# PCB_DYBoard_Collector_V1_Sh1.net
KiCad netlist of a schematic drawn in Altium Designer
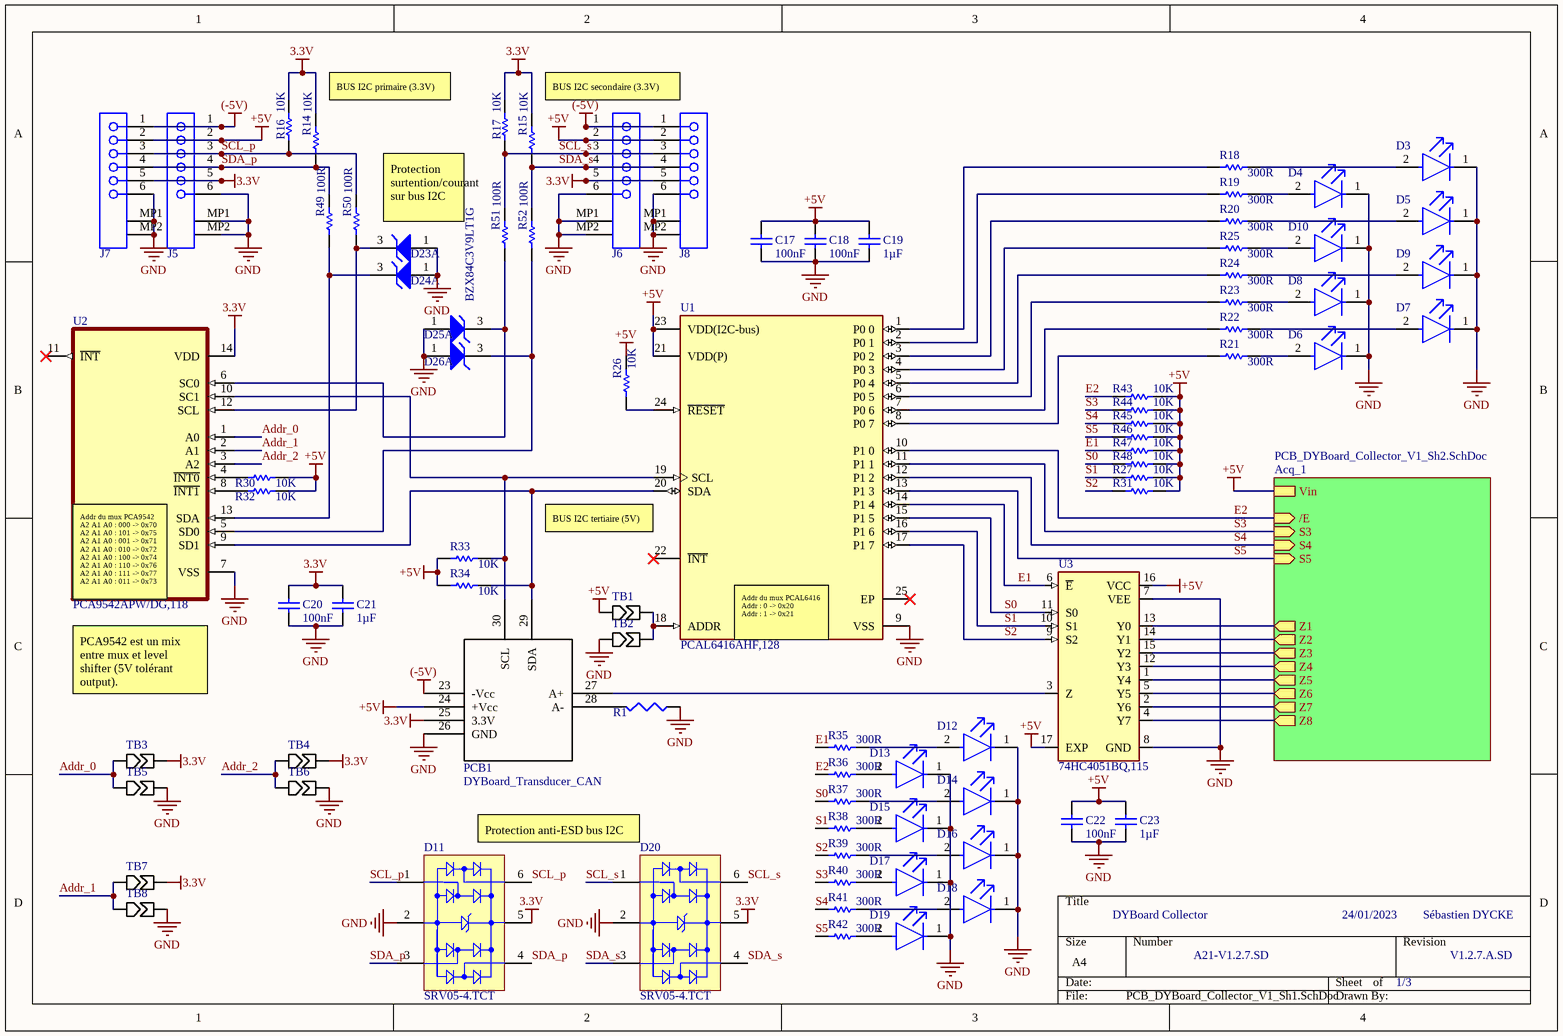
[diagram p0: PCB_DYBoard_Collector_V1_Sh1.SchDoc]

(export (version "E")
  (design (tool "Eeschema 10.0.6"))
  (components
    (comp (ref "C17")
      (value "100nF")
      (footprint "1608[0603]")
      (description "Capacitor (Semiconductor SIM Model)")
      (fields (field (name "Comment") "Cap Semi") (field (name "PUBLISHER") "Altium Limited"))
      (libsource (lib "Miscellaneous Devices") (part "Cap Semi"))
    )
    (comp (ref "C18")
      (value "100nF")
      (footprint "1608[0603]")
      (description "Capacitor (Semiconductor SIM Model)")
      (fields (field (name "Comment") "Cap Semi") (field (name "PUBLISHER") "Altium Limited"))
      (libsource (lib "Miscellaneous Devices") (part "Cap Semi"))
    )
    (comp (ref "C19")
      (value "1µF")
      (footprint "1608[0603]")
      (description "Capacitor (Semiconductor SIM Model)")
      (fields (field (name "Comment") "Cap Semi") (field (name "PUBLISHER") "Altium Limited"))
      (libsource (lib "Miscellaneous Devices") (part "Cap Semi"))
    )
    (comp (ref "C20")
      (value "100nF")
      (footprint "1608[0603]")
      (description "Capacitor (Semiconductor SIM Model)")
      (fields (field (name "Comment") "Cap Semi") (field (name "PUBLISHER") "Altium Limited"))
      (libsource (lib "Miscellaneous Devices") (part "Cap Semi"))
    )
    (comp (ref "C21")
      (value "1µF")
      (footprint "1608[0603]")
      (description "Capacitor (Semiconductor SIM Model)")
      (fields (field (name "Comment") "Cap Semi") (field (name "PUBLISHER") "Altium Limited"))
      (libsource (lib "Miscellaneous Devices") (part "Cap Semi"))
    )
    (comp (ref "C22")
      (value "100nF")
      (footprint "1608[0603]")
      (description "Capacitor (Semiconductor SIM Model)")
      (fields (field (name "Comment") "Cap Semi") (field (name "PUBLISHER") "Altium Limited"))
      (libsource (lib "Miscellaneous Devices") (part "Cap Semi"))
    )
    (comp (ref "C23")
      (value "1µF")
      (footprint "1608[0603]")
      (description "Capacitor (Semiconductor SIM Model)")
      (fields (field (name "Comment") "Cap Semi") (field (name "PUBLISHER") "Altium Limited"))
      (libsource (lib "Miscellaneous Devices") (part "Cap Semi"))
    )
    (comp (ref "D3")
      (value "LTST-C191TBKT")
      (footprint "FP-LTST-C191TBKT-MFG")
      (description "LED BLUE CLEAR CHIP SMD")
      (libsource (lib "Altium Content Vault") (part "8706943c75ba83719d021d2fdc84c58"))
    )
    (comp (ref "D4")
      (value "LTST-C191TBKT")
      (footprint "FP-LTST-C191TBKT-MFG")
      (description "LED BLUE CLEAR CHIP SMD")
      (libsource (lib "Altium Content Vault") (part "8706943c75ba83719d021d2fdc84c58"))
    )
    (comp (ref "D5")
      (value "LTST-C191TBKT")
      (footprint "FP-LTST-C191TBKT-MFG")
      (description "LED BLUE CLEAR CHIP SMD")
      (libsource (lib "Altium Content Vault") (part "8706943c75ba83719d021d2fdc84c58"))
    )
    (comp (ref "D6")
      (value "LTST-C191TBKT")
      (footprint "FP-LTST-C191TBKT-MFG")
      (description "LED BLUE CLEAR CHIP SMD")
      (libsource (lib "Altium Content Vault") (part "8706943c75ba83719d021d2fdc84c58"))
    )
    (comp (ref "D7")
      (value "LTST-C191TBKT")
      (footprint "FP-LTST-C191TBKT-MFG")
      (description "LED BLUE CLEAR CHIP SMD")
      (libsource (lib "Altium Content Vault") (part "8706943c75ba83719d021d2fdc84c58"))
    )
    (comp (ref "D8")
      (value "LTST-C191TBKT")
      (footprint "FP-LTST-C191TBKT-MFG")
      (description "LED BLUE CLEAR CHIP SMD")
      (libsource (lib "Altium Content Vault") (part "8706943c75ba83719d021d2fdc84c58"))
    )
    (comp (ref "D9")
      (value "LTST-C191TBKT")
      (footprint "FP-LTST-C191TBKT-MFG")
      (description "LED BLUE CLEAR CHIP SMD")
      (libsource (lib "Altium Content Vault") (part "8706943c75ba83719d021d2fdc84c58"))
    )
    (comp (ref "D10")
      (value "LTST-C191TBKT")
      (footprint "FP-LTST-C191TBKT-MFG")
      (description "LED BLUE CLEAR CHIP SMD")
      (libsource (lib "Altium Content Vault") (part "8706943c75ba83719d021d2fdc84c58"))
    )
    (comp (ref "D11")
      (value "SRV05-4.TCT")
      (footprint "SMTC-SOT23-6_V")
      (fields (field (name "MANUFACTURER") "Semtech"))
      (libsource (lib "Altium Content Vault") (part "STM-USB_DVI_HDMIULC6-4SC6X-SOT23-6L"))
    )
    (comp (ref "D12")
      (value "LTST-C191TBKT")
      (footprint "FP-LTST-C191TBKT-MFG")
      (description "LED BLUE CLEAR CHIP SMD")
      (libsource (lib "Altium Content Vault") (part "8706943c75ba83719d021d2fdc84c58"))
    )
    (comp (ref "D13")
      (value "LTST-C191TBKT")
      (footprint "FP-LTST-C191TBKT-MFG")
      (description "LED BLUE CLEAR CHIP SMD")
      (libsource (lib "Altium Content Vault") (part "8706943c75ba83719d021d2fdc84c58"))
    )
    (comp (ref "D14")
      (value "LTST-C191TBKT")
      (footprint "FP-LTST-C191TBKT-MFG")
      (description "LED BLUE CLEAR CHIP SMD")
      (libsource (lib "Altium Content Vault") (part "8706943c75ba83719d021d2fdc84c58"))
    )
    (comp (ref "D15")
      (value "LTST-C191TBKT")
      (footprint "FP-LTST-C191TBKT-MFG")
      (description "LED BLUE CLEAR CHIP SMD")
      (libsource (lib "Altium Content Vault") (part "8706943c75ba83719d021d2fdc84c58"))
    )
    (comp (ref "D16")
      (value "LTST-C191TBKT")
      (footprint "FP-LTST-C191TBKT-MFG")
      (description "LED BLUE CLEAR CHIP SMD")
      (libsource (lib "Altium Content Vault") (part "8706943c75ba83719d021d2fdc84c58"))
    )
    (comp (ref "D17")
      (value "LTST-C191TBKT")
      (footprint "FP-LTST-C191TBKT-MFG")
      (description "LED BLUE CLEAR CHIP SMD")
      (libsource (lib "Altium Content Vault") (part "8706943c75ba83719d021d2fdc84c58"))
    )
    (comp (ref "D18")
      (value "LTST-C191TBKT")
      (footprint "FP-LTST-C191TBKT-MFG")
      (description "LED BLUE CLEAR CHIP SMD")
      (libsource (lib "Altium Content Vault") (part "8706943c75ba83719d021d2fdc84c58"))
    )
    (comp (ref "D19")
      (value "LTST-C191TBKT")
      (footprint "FP-LTST-C191TBKT-MFG")
      (description "LED BLUE CLEAR CHIP SMD")
      (libsource (lib "Altium Content Vault") (part "8706943c75ba83719d021d2fdc84c58"))
    )
    (comp (ref "D20")
      (value "SRV05-4.TCT")
      (footprint "SMTC-SOT23-6_V")
      (fields (field (name "MANUFACTURER") "Semtech"))
      (libsource (lib "Altium Content Vault") (part "STM-USB_DVI_HDMIULC6-4SC6X-SOT23-6L"))
    )
    (comp (ref "D23")
      (value "BZX84C3V9LT1G")
      (footprint "ONSC-SOT-23-3-318-08_V")
      (description "Zener Voltage Regulator, 225 mW, 3-Pin SOT-23, Pb-Free, Tape and Reel")
      (fields (field (name "MANUFACTURER") "On Semiconductor"))
      (libsource (lib "Altium Content Vault") (part "ONSC-A1K3-3"))
    )
    (comp (ref "D24")
      (value "BZX84C3V9LT1G")
      (footprint "ONSC-SOT-23-3-318-08_V")
      (description "Zener Voltage Regulator, 225 mW, 3-Pin SOT-23, Pb-Free, Tape and Reel")
      (fields (field (name "MANUFACTURER") "On Semiconductor"))
      (libsource (lib "Altium Content Vault") (part "ONSC-A1K3-3"))
    )
    (comp (ref "D25")
      (value "BZX84C3V9LT1G")
      (footprint "ONSC-SOT-23-3-318-08_V")
      (description "Zener Voltage Regulator, 225 mW, 3-Pin SOT-23, Pb-Free, Tape and Reel")
      (fields (field (name "MANUFACTURER") "On Semiconductor"))
      (libsource (lib "") (part "ONSC-A1K3-3_1"))
    )
    (comp (ref "D26")
      (value "BZX84C3V9LT1G")
      (footprint "ONSC-SOT-23-3-318-08_V")
      (description "Zener Voltage Regulator, 225 mW, 3-Pin SOT-23, Pb-Free, Tape and Reel")
      (fields (field (name "MANUFACTURER") "On Semiconductor"))
      (libsource (lib "") (part "ONSC-A1K3-3_1"))
    )
    (comp (ref "J5")
      (value "SEB_MOLeX_6p")
      (footprint "SEB_MOLeX_6p")
      (libsource (lib "Lib_Altium_Sebastien_DYCKE") (part "SEB_MOLeX_6p"))
    )
    (comp (ref "J6")
      (value "SEB_MOLeX_6p")
      (footprint "SEB_MOLeX_6p")
      (libsource (lib "") (part "SEB_MOLeX_6p_1"))
    )
    (comp (ref "J7")
      (value "SEB_MOLeX_6p")
      (footprint "SEB_MOLeX_6p")
      (libsource (lib "Lib_Altium_Sebastien_DYCKE") (part "SEB_MOLeX_6p"))
    )
    (comp (ref "J8")
      (value "SEB_MOLeX_6p")
      (footprint "SEB_MOLeX_6p")
      (libsource (lib "") (part "SEB_MOLeX_6p_1"))
    )
    (comp (ref "PCB1")
      (value "DYBoard_Transducer_CAN")
      (footprint "DYBoard_Transducer_CAN")
      (libsource (lib "Lib_Altium_Sebastien_DYCKE") (part "DYBoard_Transducer_CAN"))
    )
    (comp (ref "R1")
      (value "Res3")
      (footprint "J1-0603")
      (description "Resistor")
      (fields (field (name "PUBLISHER") "Altium Limited"))
      (libsource (lib "Miscellaneous Devices") (part "Res3"))
    )
    (comp (ref "R14")
      (value "10K")
      (footprint "RESC1609X60X30LL10T20")
      (fields (field (name "PART NUMBER") "RCWE0603R560FKEA") (field (name "MANUFACTURER") "Vishay Dale"))
      (libsource (lib "Altium Content Vault") (part "RES"))
    )
    (comp (ref "R15")
      (value "10K")
      (footprint "RESC1609X60X30LL10T20")
      (fields (field (name "PART NUMBER") "RCWE0603R560FKEA") (field (name "MANUFACTURER") "Vishay Dale"))
      (libsource (lib "Altium Content Vault") (part "RES"))
    )
    (comp (ref "R16")
      (value "10K")
      (footprint "RESC1609X60X30LL10T20")
      (fields (field (name "PART NUMBER") "RCWE0603R560FKEA") (field (name "MANUFACTURER") "Vishay Dale"))
      (libsource (lib "Altium Content Vault") (part "RES"))
    )
    (comp (ref "R17")
      (value "10K")
      (footprint "RESC1609X60X30LL10T20")
      (fields (field (name "PART NUMBER") "RCWE0603R560FKEA") (field (name "MANUFACTURER") "Vishay Dale"))
      (libsource (lib "Altium Content Vault") (part "RES"))
    )
    (comp (ref "R18")
      (value "300R")
      (footprint "RESC1609X60X30LL10T20")
      (fields (field (name "PART NUMBER") "RCWE0603R560FKEA") (field (name "MANUFACTURER") "Vishay Dale"))
      (libsource (lib "Altium Content Vault") (part "RES"))
    )
    (comp (ref "R19")
      (value "300R")
      (footprint "RESC1609X60X30LL10T20")
      (fields (field (name "PART NUMBER") "RCWE0603R560FKEA") (field (name "MANUFACTURER") "Vishay Dale"))
      (libsource (lib "Altium Content Vault") (part "RES"))
    )
    (comp (ref "R20")
      (value "300R")
      (footprint "RESC1609X60X30LL10T20")
      (fields (field (name "PART NUMBER") "RCWE0603R560FKEA") (field (name "MANUFACTURER") "Vishay Dale"))
      (libsource (lib "Altium Content Vault") (part "RES"))
    )
    (comp (ref "R21")
      (value "300R")
      (footprint "RESC1609X60X30LL10T20")
      (fields (field (name "PART NUMBER") "RCWE0603R560FKEA") (field (name "MANUFACTURER") "Vishay Dale"))
      (libsource (lib "Altium Content Vault") (part "RES"))
    )
    (comp (ref "R22")
      (value "300R")
      (footprint "RESC1609X60X30LL10T20")
      (fields (field (name "PART NUMBER") "RCWE0603R560FKEA") (field (name "MANUFACTURER") "Vishay Dale"))
      (libsource (lib "Altium Content Vault") (part "RES"))
    )
    (comp (ref "R23")
      (value "300R")
      (footprint "RESC1609X60X30LL10T20")
      (fields (field (name "PART NUMBER") "RCWE0603R560FKEA") (field (name "MANUFACTURER") "Vishay Dale"))
      (libsource (lib "Altium Content Vault") (part "RES"))
    )
    (comp (ref "R24")
      (value "300R")
      (footprint "RESC1609X60X30LL10T20")
      (fields (field (name "PART NUMBER") "RCWE0603R560FKEA") (field (name "MANUFACTURER") "Vishay Dale"))
      (libsource (lib "Altium Content Vault") (part "RES"))
    )
    (comp (ref "R25")
      (value "300R")
      (footprint "RESC1609X60X30LL10T20")
      (fields (field (name "PART NUMBER") "RCWE0603R560FKEA") (field (name "MANUFACTURER") "Vishay Dale"))
      (libsource (lib "Altium Content Vault") (part "RES"))
    )
    (comp (ref "R26")
      (value "10K")
      (footprint "RESC1609X60X30LL10T20")
      (fields (field (name "PART NUMBER") "RCWE0603R560FKEA") (field (name "MANUFACTURER") "Vishay Dale"))
      (libsource (lib "Altium Content Vault") (part "RES"))
    )
    (comp (ref "R27")
      (value "10K")
      (footprint "RESC1609X60X30LL10T20")
      (fields (field (name "PART NUMBER") "RCWE0603R560FKEA") (field (name "MANUFACTURER") "Vishay Dale"))
      (libsource (lib "Altium Content Vault") (part "RES"))
    )
    (comp (ref "R30")
      (value "10K")
      (footprint "RESC1609X60X30LL10T20")
      (fields (field (name "PART NUMBER") "RCWE0603R560FKEA") (field (name "MANUFACTURER") "Vishay Dale"))
      (libsource (lib "Altium Content Vault") (part "RES"))
    )
    (comp (ref "R31")
      (value "10K")
      (footprint "RESC1609X60X30LL10T20")
      (fields (field (name "PART NUMBER") "RCWE0603R560FKEA") (field (name "MANUFACTURER") "Vishay Dale"))
      (libsource (lib "Altium Content Vault") (part "RES"))
    )
    (comp (ref "R32")
      (value "10K")
      (footprint "RESC1609X60X30LL10T20")
      (fields (field (name "PART NUMBER") "RCWE0603R560FKEA") (field (name "MANUFACTURER") "Vishay Dale"))
      (libsource (lib "Altium Content Vault") (part "RES"))
    )
    (comp (ref "R33")
      (value "10K")
      (footprint "RESC1609X60X30LL10T20")
      (fields (field (name "PART NUMBER") "RCWE0603R560FKEA") (field (name "MANUFACTURER") "Vishay Dale"))
      (libsource (lib "Altium Content Vault") (part "RES"))
    )
    (comp (ref "R34")
      (value "10K")
      (footprint "RESC1609X60X30LL10T20")
      (fields (field (name "PART NUMBER") "RCWE0603R560FKEA") (field (name "MANUFACTURER") "Vishay Dale"))
      (libsource (lib "Altium Content Vault") (part "RES"))
    )
    (comp (ref "R35")
      (value "300R")
      (footprint "RESC1609X60X30LL10T20")
      (fields (field (name "PART NUMBER") "RCWE0603R560FKEA") (field (name "MANUFACTURER") "Vishay Dale"))
      (libsource (lib "Altium Content Vault") (part "RES"))
    )
    (comp (ref "R36")
      (value "300R")
      (footprint "RESC1609X60X30LL10T20")
      (fields (field (name "PART NUMBER") "RCWE0603R560FKEA") (field (name "MANUFACTURER") "Vishay Dale"))
      (libsource (lib "Altium Content Vault") (part "RES"))
    )
    (comp (ref "R37")
      (value "300R")
      (footprint "RESC1609X60X30LL10T20")
      (fields (field (name "PART NUMBER") "RCWE0603R560FKEA") (field (name "MANUFACTURER") "Vishay Dale"))
      (libsource (lib "Altium Content Vault") (part "RES"))
    )
    (comp (ref "R38")
      (value "300R")
      (footprint "RESC1609X60X30LL10T20")
      (fields (field (name "PART NUMBER") "RCWE0603R560FKEA") (field (name "MANUFACTURER") "Vishay Dale"))
      (libsource (lib "Altium Content Vault") (part "RES"))
    )
    (comp (ref "R39")
      (value "300R")
      (footprint "RESC1609X60X30LL10T20")
      (fields (field (name "PART NUMBER") "RCWE0603R560FKEA") (field (name "MANUFACTURER") "Vishay Dale"))
      (libsource (lib "Altium Content Vault") (part "RES"))
    )
    (comp (ref "R40")
      (value "300R")
      (footprint "RESC1609X60X30LL10T20")
      (fields (field (name "PART NUMBER") "RCWE0603R560FKEA") (field (name "MANUFACTURER") "Vishay Dale"))
      (libsource (lib "Altium Content Vault") (part "RES"))
    )
    (comp (ref "R41")
      (value "300R")
      (footprint "RESC1609X60X30LL10T20")
      (fields (field (name "PART NUMBER") "RCWE0603R560FKEA") (field (name "MANUFACTURER") "Vishay Dale"))
      (libsource (lib "Altium Content Vault") (part "RES"))
    )
    (comp (ref "R42")
      (value "300R")
      (footprint "RESC1609X60X30LL10T20")
      (fields (field (name "PART NUMBER") "RCWE0603R560FKEA") (field (name "MANUFACTURER") "Vishay Dale"))
      (libsource (lib "Altium Content Vault") (part "RES"))
    )
    (comp (ref "R43")
      (value "10K")
      (footprint "RESC1609X60X30LL10T20")
      (fields (field (name "PART NUMBER") "RCWE0603R560FKEA") (field (name "MANUFACTURER") "Vishay Dale"))
      (libsource (lib "Altium Content Vault") (part "RES"))
    )
    (comp (ref "R44")
      (value "10K")
      (footprint "RESC1609X60X30LL10T20")
      (fields (field (name "PART NUMBER") "RCWE0603R560FKEA") (field (name "MANUFACTURER") "Vishay Dale"))
      (libsource (lib "Altium Content Vault") (part "RES"))
    )
    (comp (ref "R45")
      (value "10K")
      (footprint "RESC1609X60X30LL10T20")
      (fields (field (name "PART NUMBER") "RCWE0603R560FKEA") (field (name "MANUFACTURER") "Vishay Dale"))
      (libsource (lib "Altium Content Vault") (part "RES"))
    )
    (comp (ref "R46")
      (value "10K")
      (footprint "RESC1609X60X30LL10T20")
      (fields (field (name "PART NUMBER") "RCWE0603R560FKEA") (field (name "MANUFACTURER") "Vishay Dale"))
      (libsource (lib "Altium Content Vault") (part "RES"))
    )
    (comp (ref "R47")
      (value "10K")
      (footprint "RESC1609X60X30LL10T20")
      (fields (field (name "PART NUMBER") "RCWE0603R560FKEA") (field (name "MANUFACTURER") "Vishay Dale"))
      (libsource (lib "Altium Content Vault") (part "RES"))
    )
    (comp (ref "R48")
      (value "10K")
      (footprint "RESC1609X60X30LL10T20")
      (fields (field (name "PART NUMBER") "RCWE0603R560FKEA") (field (name "MANUFACTURER") "Vishay Dale"))
      (libsource (lib "Altium Content Vault") (part "RES"))
    )
    (comp (ref "R49")
      (value "100R")
      (footprint "RESC1609X60X30LL10T20")
      (fields (field (name "PART NUMBER") "RCWE0603R560FKEA") (field (name "MANUFACTURER") "Vishay Dale"))
      (libsource (lib "Altium Content Vault") (part "RES"))
    )
    (comp (ref "R50")
      (value "100R")
      (footprint "RESC1609X60X30LL10T20")
      (fields (field (name "PART NUMBER") "RCWE0603R560FKEA") (field (name "MANUFACTURER") "Vishay Dale"))
      (libsource (lib "Altium Content Vault") (part "RES"))
    )
    (comp (ref "R51")
      (value "100R")
      (footprint "RESC1609X60X30LL10T20")
      (fields (field (name "PART NUMBER") "RCWE0603R560FKEA") (field (name "MANUFACTURER") "Vishay Dale"))
      (libsource (lib "Altium Content Vault") (part "RES"))
    )
    (comp (ref "R52")
      (value "100R")
      (footprint "RESC1609X60X30LL10T20")
      (fields (field (name "PART NUMBER") "RCWE0603R560FKEA") (field (name "MANUFACTURER") "Vishay Dale"))
      (libsource (lib "Altium Content Vault") (part "RES"))
    )
    (comp (ref "TB1")
      (value "tin_bridge")
      (footprint "tin_bridge")
      (libsource (lib "Lib_Altium_Sebastien_DYCKE") (part "tin_bridge"))
    )
    (comp (ref "TB2")
      (value "tin_bridge")
      (footprint "tin_bridge")
      (libsource (lib "Lib_Altium_Sebastien_DYCKE") (part "tin_bridge"))
    )
    (comp (ref "TB3")
      (value "tin_bridge")
      (footprint "tin_bridge")
      (libsource (lib "Lib_Altium_Sebastien_DYCKE") (part "tin_bridge"))
    )
    (comp (ref "TB4")
      (value "tin_bridge")
      (footprint "tin_bridge")
      (libsource (lib "Lib_Altium_Sebastien_DYCKE") (part "tin_bridge"))
    )
    (comp (ref "TB5")
      (value "tin_bridge")
      (footprint "tin_bridge")
      (libsource (lib "Lib_Altium_Sebastien_DYCKE") (part "tin_bridge"))
    )
    (comp (ref "TB6")
      (value "tin_bridge")
      (footprint "tin_bridge")
      (libsource (lib "Lib_Altium_Sebastien_DYCKE") (part "tin_bridge"))
    )
    (comp (ref "TB7")
      (value "tin_bridge")
      (footprint "tin_bridge")
      (libsource (lib "Lib_Altium_Sebastien_DYCKE") (part "tin_bridge"))
    )
    (comp (ref "TB8")
      (value "tin_bridge")
      (footprint "tin_bridge")
      (libsource (lib "Lib_Altium_Sebastien_DYCKE") (part "tin_bridge"))
    )
    (comp (ref "U1")
      (value "PCAL6416AHF,128")
      (footprint "FP-SOT994-1-MFG")
      (description "IC I/O EXPANDER 16BIT 24HWQFN")
      (fields
        (field (name "MANUFACTURER") "NXP Semiconductors")
        (field (name "OCTOPART") "https://octopart.com/pcal6416ahf%2C128-nxp+semiconductors-24406122")
      )
      (libsource (lib "Altium Content Vault") (part "aa512ef89758d57dfcc452c0987c77d"))
    )
    (comp (ref "U2")
      (value "PCA9542APW/DG,118")
      (footprint "SOP65P640X110-14N")
      (description "2-channel I2C-bus multiplexer and interrupt logic")
      (libsource (lib "PCA9542APW_DG_118") (part "PCA9542APW/DG,118"))
    )
    (comp (ref "U3")
      (value "74HC4051BQ,115")
      (footprint "QFN50P250X350X100-17N")
      (description "1 Circuit IC Switch 8:1 120Ohm 16-DHVQFN _2.5x3.5_")
      (fields (field (name "MF") "Nexperia USA"))
      (libsource (lib "74HC4051BQ_115") (part "74HC4051BQ,115"))
    )
  )
  (nets
    (net (code "1") (name "(-5V)") (class "Default")
      (node (ref "J5") (pin "1") (pinfunction "1_1") (pintype "passive"))
      (node (ref "J6") (pin "1") (pinfunction "1_1") (pintype "passive"))
      (node (ref "J7") (pin "1") (pinfunction "1_1") (pintype "passive"))
      (node (ref "J8") (pin "1") (pinfunction "1_1") (pintype "passive"))
      (node (ref "PCB1") (pin "23") (pinfunction "-Vcc_23") (pintype "passive"))
    )
    (net (code "2") (name "+5V") (class "Default")
      (node (ref "C17") (pin "2") (pinfunction "2_2") (pintype "passive"))
      (node (ref "C18") (pin "2") (pinfunction "2_2") (pintype "passive"))
      (node (ref "C19") (pin "2") (pinfunction "2_2") (pintype "passive"))
      (node (ref "C22") (pin "2") (pinfunction "2_2") (pintype "passive"))
      (node (ref "C23") (pin "2") (pinfunction "2_2") (pintype "passive"))
      (node (ref "J5") (pin "2") (pinfunction "2_2") (pintype "passive"))
      (node (ref "J6") (pin "2") (pinfunction "2_2") (pintype "passive"))
      (node (ref "J7") (pin "2") (pinfunction "2_2") (pintype "passive"))
      (node (ref "J8") (pin "2") (pinfunction "2_2") (pintype "passive"))
      (node (ref "PCB1") (pin "24") (pinfunction "+Vcc_24") (pintype "passive"))
      (node (ref "R26") (pin "2") (pinfunction "2_2") (pintype "passive"))
      (node (ref "R27") (pin "1") (pinfunction "1_1") (pintype "passive"))
      (node (ref "R30") (pin "1") (pinfunction "1_1") (pintype "passive"))
      (node (ref "R31") (pin "1") (pinfunction "1_1") (pintype "passive"))
      (node (ref "R32") (pin "1") (pinfunction "1_1") (pintype "passive"))
      (node (ref "R33") (pin "2") (pinfunction "2_2") (pintype "passive"))
      (node (ref "R34") (pin "2") (pinfunction "2_2") (pintype "passive"))
      (node (ref "R43") (pin "1") (pinfunction "1_1") (pintype "passive"))
      (node (ref "R44") (pin "1") (pinfunction "1_1") (pintype "passive"))
      (node (ref "R45") (pin "1") (pinfunction "1_1") (pintype "passive"))
      (node (ref "R46") (pin "1") (pinfunction "1_1") (pintype "passive"))
      (node (ref "R47") (pin "1") (pinfunction "1_1") (pintype "passive"))
      (node (ref "R48") (pin "1") (pinfunction "1_1") (pintype "passive"))
      (node (ref "TB1") (pin "21") (pinfunction "21_21") (pintype "passive"))
      (node (ref "U1") (pin "21") (pinfunction "VDD(P)_21") (pintype "power_in"))
      (node (ref "U1") (pin "23") (pinfunction "VDD(I2C-bus)_23") (pintype "power_in"))
      (node (ref "U3") (pin "16") (pinfunction "VCC_16") (pintype "power_in"))
      (node (ref "U3") (pin "17") (pinfunction "EXP_17") (pintype "power_in"))
    )
    (net (code "3") (name "/Addr_0") (class "Default")
      (node (ref "TB3") (pin "21") (pinfunction "21_21") (pintype "passive"))
      (node (ref "TB5") (pin "21") (pinfunction "21_21") (pintype "passive"))
      (node (ref "U2") (pin "1") (pinfunction "A0_1") (pintype "input"))
    )
    (net (code "4") (name "/Addr_1") (class "Default")
      (node (ref "TB7") (pin "21") (pinfunction "21_21") (pintype "passive"))
      (node (ref "TB8") (pin "21") (pinfunction "21_21") (pintype "passive"))
      (node (ref "U2") (pin "2") (pinfunction "A1_2") (pintype "input"))
    )
    (net (code "5") (name "/Addr_2") (class "Default")
      (node (ref "TB4") (pin "21") (pinfunction "21_21") (pintype "passive"))
      (node (ref "TB6") (pin "21") (pinfunction "21_21") (pintype "passive"))
      (node (ref "U2") (pin "3") (pinfunction "A2_3") (pintype "input"))
    )
    (net (code "6") (name "/E1") (class "Default")
      (node (ref "R35") (pin "1") (pinfunction "1_1") (pintype "passive"))
      (node (ref "R47") (pin "2") (pinfunction "2_2") (pintype "passive"))
      (node (ref "U1") (pin "14") (pinfunction "P1_4_14") (pintype "bidirectional"))
      (node (ref "U3") (pin "6") (pinfunction "~{E}_6") (pintype "input"))
    )
    (net (code "7") (name "/E2") (class "Default")
      (node (ref "R36") (pin "1") (pinfunction "1_1") (pintype "passive"))
      (node (ref "R43") (pin "2") (pinfunction "2_2") (pintype "passive"))
      (node (ref "U1") (pin "10") (pinfunction "P1_0_10") (pintype "bidirectional"))
    )
    (net (code "8") (name "/S0") (class "Default")
      (node (ref "R37") (pin "1") (pinfunction "1_1") (pintype "passive"))
      (node (ref "R48") (pin "2") (pinfunction "2_2") (pintype "passive"))
      (node (ref "U1") (pin "15") (pinfunction "P1_5_15") (pintype "bidirectional"))
      (node (ref "U3") (pin "11") (pinfunction "S0_11") (pintype "input"))
    )
    (net (code "9") (name "/S1") (class "Default")
      (node (ref "R27") (pin "2") (pinfunction "2_2") (pintype "passive"))
      (node (ref "R38") (pin "1") (pinfunction "1_1") (pintype "passive"))
      (node (ref "U1") (pin "16") (pinfunction "P1_6_16") (pintype "bidirectional"))
      (node (ref "U3") (pin "10") (pinfunction "S1_10") (pintype "input"))
    )
    (net (code "10") (name "/S2") (class "Default")
      (node (ref "R31") (pin "2") (pinfunction "2_2") (pintype "passive"))
      (node (ref "R39") (pin "1") (pinfunction "1_1") (pintype "passive"))
      (node (ref "U1") (pin "17") (pinfunction "P1_7_17") (pintype "bidirectional"))
      (node (ref "U3") (pin "9") (pinfunction "S2_9") (pintype "input"))
    )
    (net (code "11") (name "/S3") (class "Default")
      (node (ref "R40") (pin "1") (pinfunction "1_1") (pintype "passive"))
      (node (ref "R44") (pin "2") (pinfunction "2_2") (pintype "passive"))
      (node (ref "U1") (pin "11") (pinfunction "P1_1_11") (pintype "bidirectional"))
    )
    (net (code "12") (name "/S4") (class "Default")
      (node (ref "R41") (pin "1") (pinfunction "1_1") (pintype "passive"))
      (node (ref "R45") (pin "2") (pinfunction "2_2") (pintype "passive"))
      (node (ref "U1") (pin "12") (pinfunction "P1_2_12") (pintype "bidirectional"))
    )
    (net (code "13") (name "/S5") (class "Default")
      (node (ref "R42") (pin "1") (pinfunction "1_1") (pintype "passive"))
      (node (ref "R46") (pin "2") (pinfunction "2_2") (pintype "passive"))
      (node (ref "U1") (pin "13") (pinfunction "P1_3_13") (pintype "bidirectional"))
    )
    (net (code "14") (name "/SCL_p") (class "Default")
      (node (ref "D11") (pin "1") (pinfunction "I/O_1_1") (pintype "passive"))
      (node (ref "D11") (pin "6") (pinfunction "I/O_4_6") (pintype "passive"))
      (node (ref "J5") (pin "3") (pinfunction "3_3") (pintype "passive"))
      (node (ref "J7") (pin "3") (pinfunction "3_3") (pintype "passive"))
      (node (ref "R16") (pin "1") (pinfunction "1_1") (pintype "passive"))
      (node (ref "R50") (pin "2") (pinfunction "2_2") (pintype "passive"))
    )
    (net (code "15") (name "/SCL_s") (class "Default")
      (node (ref "D20") (pin "1") (pinfunction "I/O_1_1") (pintype "passive"))
      (node (ref "D20") (pin "6") (pinfunction "I/O_4_6") (pintype "passive"))
      (node (ref "J6") (pin "3") (pinfunction "3_3") (pintype "passive"))
      (node (ref "J8") (pin "3") (pinfunction "3_3") (pintype "passive"))
      (node (ref "R17") (pin "1") (pinfunction "1_1") (pintype "passive"))
      (node (ref "R51") (pin "2") (pinfunction "2_2") (pintype "passive"))
    )
    (net (code "16") (name "/SDA_p") (class "Default")
      (node (ref "D11") (pin "3") (pinfunction "I/O_2_3") (pintype "passive"))
      (node (ref "D11") (pin "4") (pinfunction "I/O_3_4") (pintype "passive"))
      (node (ref "J5") (pin "4") (pinfunction "4_4") (pintype "passive"))
      (node (ref "J7") (pin "4") (pinfunction "4_4") (pintype "passive"))
      (node (ref "R14") (pin "1") (pinfunction "1_1") (pintype "passive"))
      (node (ref "R49") (pin "2") (pinfunction "2_2") (pintype "passive"))
    )
    (net (code "17") (name "/SDA_s") (class "Default")
      (node (ref "D20") (pin "3") (pinfunction "I/O_2_3") (pintype "passive"))
      (node (ref "D20") (pin "4") (pinfunction "I/O_3_4") (pintype "passive"))
      (node (ref "J6") (pin "4") (pinfunction "4_4") (pintype "passive"))
      (node (ref "J8") (pin "4") (pinfunction "4_4") (pintype "passive"))
      (node (ref "R15") (pin "1") (pinfunction "1_1") (pintype "passive"))
      (node (ref "R52") (pin "2") (pinfunction "2_2") (pintype "passive"))
    )
    (net (code "18") (name "/Z1") (class "Default")
      (node (ref "U3") (pin "13") (pinfunction "Y0_13") (pintype "bidirectional"))
    )
    (net (code "19") (name "/Z2") (class "Default")
      (node (ref "U3") (pin "14") (pinfunction "Y1_14") (pintype "bidirectional"))
    )
    (net (code "20") (name "/Z3") (class "Default")
      (node (ref "U3") (pin "15") (pinfunction "Y2_15") (pintype "bidirectional"))
    )
    (net (code "21") (name "/Z4") (class "Default")
      (node (ref "U3") (pin "12") (pinfunction "Y3_12") (pintype "bidirectional"))
    )
    (net (code "22") (name "/Z5") (class "Default")
      (node (ref "U3") (pin "1") (pinfunction "Y4_1") (pintype "bidirectional"))
    )
    (net (code "23") (name "/Z6") (class "Default")
      (node (ref "U3") (pin "5") (pinfunction "Y5_5") (pintype "bidirectional"))
    )
    (net (code "24") (name "/Z7") (class "Default")
      (node (ref "U3") (pin "2") (pinfunction "Y6_2") (pintype "bidirectional"))
    )
    (net (code "25") (name "/Z8") (class "Default")
      (node (ref "U3") (pin "4") (pinfunction "Y7_4") (pintype "bidirectional"))
    )
    (net (code "26") (name "3.3V") (class "Default")
      (node (ref "C20") (pin "2") (pinfunction "2_2") (pintype "passive"))
      (node (ref "C21") (pin "2") (pinfunction "2_2") (pintype "passive"))
      (node (ref "D11") (pin "5") (pinfunction "VBUS_5") (pintype "passive"))
      (node (ref "D20") (pin "5") (pinfunction "VBUS_5") (pintype "passive"))
      (node (ref "J5") (pin "5") (pinfunction "5_5") (pintype "passive"))
      (node (ref "J6") (pin "5") (pinfunction "5_5") (pintype "passive"))
      (node (ref "J7") (pin "5") (pinfunction "5_5") (pintype "passive"))
      (node (ref "J8") (pin "5") (pinfunction "5_5") (pintype "passive"))
      (node (ref "PCB1") (pin "25") (pinfunction "3.3V_25") (pintype "passive"))
      (node (ref "R14") (pin "2") (pinfunction "2_2") (pintype "passive"))
      (node (ref "R15") (pin "2") (pinfunction "2_2") (pintype "passive"))
      (node (ref "R16") (pin "2") (pinfunction "2_2") (pintype "passive"))
      (node (ref "R17") (pin "2") (pinfunction "2_2") (pintype "passive"))
      (node (ref "TB3") (pin "22") (pinfunction "22_22") (pintype "passive"))
      (node (ref "TB4") (pin "22") (pinfunction "22_22") (pintype "passive"))
      (node (ref "TB7") (pin "22") (pinfunction "22_22") (pintype "passive"))
      (node (ref "U2") (pin "14") (pinfunction "VDD_14") (pintype "power_in"))
    )
    (net (code "27") (name "GND") (class "Default")
      (node (ref "C17") (pin "1") (pinfunction "1_1") (pintype "passive"))
      (node (ref "C18") (pin "1") (pinfunction "1_1") (pintype "passive"))
      (node (ref "C19") (pin "1") (pinfunction "1_1") (pintype "passive"))
      (node (ref "C20") (pin "1") (pinfunction "1_1") (pintype "passive"))
      (node (ref "C21") (pin "1") (pinfunction "1_1") (pintype "passive"))
      (node (ref "C22") (pin "1") (pinfunction "1_1") (pintype "passive"))
      (node (ref "C23") (pin "1") (pinfunction "1_1") (pintype "passive"))
      (node (ref "D10") (pin "1") (pinfunction "C_1") (pintype "passive"))
      (node (ref "D11") (pin "2") (pinfunction "GND_2") (pintype "passive"))
      (node (ref "D12") (pin "1") (pinfunction "C_1") (pintype "passive"))
      (node (ref "D13") (pin "1") (pinfunction "C_1") (pintype "passive"))
      (node (ref "D14") (pin "1") (pinfunction "C_1") (pintype "passive"))
      (node (ref "D15") (pin "1") (pinfunction "C_1") (pintype "passive"))
      (node (ref "D16") (pin "1") (pinfunction "C_1") (pintype "passive"))
      (node (ref "D17") (pin "1") (pinfunction "C_1") (pintype "passive"))
      (node (ref "D18") (pin "1") (pinfunction "C_1") (pintype "passive"))
      (node (ref "D19") (pin "1") (pinfunction "C_1") (pintype "passive"))
      (node (ref "D20") (pin "2") (pinfunction "GND_2") (pintype "passive"))
      (node (ref "D23") (pin "1") (pinfunction "A_1") (pintype "passive"))
      (node (ref "D24") (pin "1") (pinfunction "A_1") (pintype "passive"))
      (node (ref "D25") (pin "1") (pinfunction "A_1") (pintype "passive"))
      (node (ref "D26") (pin "1") (pinfunction "A_1") (pintype "passive"))
      (node (ref "D3") (pin "1") (pinfunction "C_1") (pintype "passive"))
      (node (ref "D4") (pin "1") (pinfunction "C_1") (pintype "passive"))
      (node (ref "D5") (pin "1") (pinfunction "C_1") (pintype "passive"))
      (node (ref "D6") (pin "1") (pinfunction "C_1") (pintype "passive"))
      (node (ref "D7") (pin "1") (pinfunction "C_1") (pintype "passive"))
      (node (ref "D8") (pin "1") (pinfunction "C_1") (pintype "passive"))
      (node (ref "D9") (pin "1") (pinfunction "C_1") (pintype "passive"))
      (node (ref "J5") (pin "6") (pinfunction "6_6") (pintype "passive"))
      (node (ref "J5") (pin "MP1") (pinfunction "MP1_MP1") (pintype "passive"))
      (node (ref "J5") (pin "MP2") (pinfunction "MP2_MP2") (pintype "passive"))
      (node (ref "J6") (pin "6") (pinfunction "6_6") (pintype "passive"))
      (node (ref "J6") (pin "MP1") (pinfunction "MP1_MP1") (pintype "passive"))
      (node (ref "J6") (pin "MP2") (pinfunction "MP2_MP2") (pintype "passive"))
      (node (ref "J7") (pin "6") (pinfunction "6_6") (pintype "passive"))
      (node (ref "J7") (pin "MP1") (pinfunction "MP1_MP1") (pintype "passive"))
      (node (ref "J7") (pin "MP2") (pinfunction "MP2_MP2") (pintype "passive"))
      (node (ref "J8") (pin "6") (pinfunction "6_6") (pintype "passive"))
      (node (ref "J8") (pin "MP1") (pinfunction "MP1_MP1") (pintype "passive"))
      (node (ref "J8") (pin "MP2") (pinfunction "MP2_MP2") (pintype "passive"))
      (node (ref "PCB1") (pin "26") (pinfunction "GND_26") (pintype "passive"))
      (node (ref "R1") (pin "2") (pinfunction "2_2") (pintype "passive"))
      (node (ref "TB2") (pin "21") (pinfunction "21_21") (pintype "passive"))
      (node (ref "TB5") (pin "22") (pinfunction "22_22") (pintype "passive"))
      (node (ref "TB6") (pin "22") (pinfunction "22_22") (pintype "passive"))
      (node (ref "TB8") (pin "22") (pinfunction "22_22") (pintype "passive"))
      (node (ref "U1") (pin "9") (pinfunction "VSS_9") (pintype "power_in"))
      (node (ref "U2") (pin "7") (pinfunction "VSS_7") (pintype "passive"))
      (node (ref "U3") (pin "7") (pinfunction "VEE_7") (pintype "power_in"))
      (node (ref "U3") (pin "8") (pinfunction "GND_8") (pintype "power_in"))
    )
    (net (code "28") (name "Net-(D3-A)") (class "Default")
      (node (ref "D3") (pin "2") (pinfunction "A_2") (pintype "passive"))
      (node (ref "R18") (pin "2") (pinfunction "2_2") (pintype "passive"))
    )
    (net (code "29") (name "Net-(D4-A)") (class "Default")
      (node (ref "D4") (pin "2") (pinfunction "A_2") (pintype "passive"))
      (node (ref "R19") (pin "2") (pinfunction "2_2") (pintype "passive"))
    )
    (net (code "30") (name "Net-(D5-A)") (class "Default")
      (node (ref "D5") (pin "2") (pinfunction "A_2") (pintype "passive"))
      (node (ref "R20") (pin "2") (pinfunction "2_2") (pintype "passive"))
    )
    (net (code "31") (name "Net-(D6-A)") (class "Default")
      (node (ref "D6") (pin "2") (pinfunction "A_2") (pintype "passive"))
      (node (ref "R21") (pin "2") (pinfunction "2_2") (pintype "passive"))
    )
    (net (code "32") (name "Net-(D7-A)") (class "Default")
      (node (ref "D7") (pin "2") (pinfunction "A_2") (pintype "passive"))
      (node (ref "R22") (pin "2") (pinfunction "2_2") (pintype "passive"))
    )
    (net (code "33") (name "Net-(D8-A)") (class "Default")
      (node (ref "D8") (pin "2") (pinfunction "A_2") (pintype "passive"))
      (node (ref "R23") (pin "2") (pinfunction "2_2") (pintype "passive"))
    )
    (net (code "34") (name "Net-(D9-A)") (class "Default")
      (node (ref "D9") (pin "2") (pinfunction "A_2") (pintype "passive"))
      (node (ref "R24") (pin "2") (pinfunction "2_2") (pintype "passive"))
    )
    (net (code "35") (name "Net-(D10-A)") (class "Default")
      (node (ref "D10") (pin "2") (pinfunction "A_2") (pintype "passive"))
      (node (ref "R25") (pin "2") (pinfunction "2_2") (pintype "passive"))
    )
    (net (code "36") (name "Net-(D12-A)") (class "Default")
      (node (ref "D12") (pin "2") (pinfunction "A_2") (pintype "passive"))
      (node (ref "R35") (pin "2") (pinfunction "2_2") (pintype "passive"))
    )
    (net (code "37") (name "Net-(D13-A)") (class "Default")
      (node (ref "D13") (pin "2") (pinfunction "A_2") (pintype "passive"))
      (node (ref "R36") (pin "2") (pinfunction "2_2") (pintype "passive"))
    )
    (net (code "38") (name "Net-(D14-A)") (class "Default")
      (node (ref "D14") (pin "2") (pinfunction "A_2") (pintype "passive"))
      (node (ref "R37") (pin "2") (pinfunction "2_2") (pintype "passive"))
    )
    (net (code "39") (name "Net-(D15-A)") (class "Default")
      (node (ref "D15") (pin "2") (pinfunction "A_2") (pintype "passive"))
      (node (ref "R38") (pin "2") (pinfunction "2_2") (pintype "passive"))
    )
    (net (code "40") (name "Net-(D16-A)") (class "Default")
      (node (ref "D16") (pin "2") (pinfunction "A_2") (pintype "passive"))
      (node (ref "R39") (pin "2") (pinfunction "2_2") (pintype "passive"))
    )
    (net (code "41") (name "Net-(D17-A)") (class "Default")
      (node (ref "D17") (pin "2") (pinfunction "A_2") (pintype "passive"))
      (node (ref "R40") (pin "2") (pinfunction "2_2") (pintype "passive"))
    )
    (net (code "42") (name "Net-(D18-A)") (class "Default")
      (node (ref "D18") (pin "2") (pinfunction "A_2") (pintype "passive"))
      (node (ref "R41") (pin "2") (pinfunction "2_2") (pintype "passive"))
    )
    (net (code "43") (name "Net-(D19-A)") (class "Default")
      (node (ref "D19") (pin "2") (pinfunction "A_2") (pintype "passive"))
      (node (ref "R42") (pin "2") (pinfunction "2_2") (pintype "passive"))
    )
    (net (code "44") (name "Net-(D23A-K)") (class "Default")
      (node (ref "D23") (pin "3") (pinfunction "K_3") (pintype "passive"))
      (node (ref "R50") (pin "1") (pinfunction "1_1") (pintype "passive"))
      (node (ref "U2") (pin "12") (pinfunction "SCL_12") (pintype "input"))
    )
    (net (code "45") (name "Net-(D24A-K)") (class "Default")
      (node (ref "D24") (pin "3") (pinfunction "K_3") (pintype "passive"))
      (node (ref "R49") (pin "1") (pinfunction "1_1") (pintype "passive"))
      (node (ref "U2") (pin "13") (pinfunction "SDA_13") (pintype "input"))
    )
    (net (code "46") (name "Net-(D25A-K)") (class "Default")
      (node (ref "D25") (pin "3") (pinfunction "K_3") (pintype "passive"))
      (node (ref "R51") (pin "1") (pinfunction "1_1") (pintype "passive"))
      (node (ref "U2") (pin "6") (pinfunction "SC0_6") (pintype "input"))
    )
    (net (code "47") (name "Net-(D26A-K)") (class "Default")
      (node (ref "D26") (pin "3") (pinfunction "K_3") (pintype "passive"))
      (node (ref "R52") (pin "1") (pinfunction "1_1") (pintype "passive"))
      (node (ref "U2") (pin "5") (pinfunction "SD0_5") (pintype "input"))
    )
    (net (code "48") (name "Net-(PCB1-A+)") (class "Default")
      (node (ref "PCB1") (pin "27") (pinfunction "A+_27") (pintype "passive"))
      (node (ref "U3") (pin "3") (pinfunction "Z_3") (pintype "bidirectional"))
    )
    (net (code "49") (name "Net-(PCB1-A-)") (class "Default")
      (node (ref "PCB1") (pin "28") (pinfunction "A-_28") (pintype "passive"))
      (node (ref "R1") (pin "1") (pinfunction "1_1") (pintype "passive"))
    )
    (net (code "50") (name "Net-(PCB1-SCL)") (class "Default")
      (node (ref "PCB1") (pin "30") (pinfunction "SCL_30") (pintype "passive"))
      (node (ref "R33") (pin "1") (pinfunction "1_1") (pintype "passive"))
      (node (ref "U1") (pin "19") (pinfunction "SCL_19") (pintype "input"))
      (node (ref "U2") (pin "10") (pinfunction "SC1_10") (pintype "input"))
    )
    (net (code "51") (name "Net-(PCB1-SDA)") (class "Default")
      (node (ref "PCB1") (pin "29") (pinfunction "SDA_29") (pintype "passive"))
      (node (ref "R34") (pin "1") (pinfunction "1_1") (pintype "passive"))
      (node (ref "U1") (pin "20") (pinfunction "SDA_20") (pintype "bidirectional"))
      (node (ref "U2") (pin "9") (pinfunction "SD1_9") (pintype "input"))
    )
    (net (code "52") (name "Net-(U1-ADDR)") (class "Default")
      (node (ref "TB1") (pin "22") (pinfunction "22_22") (pintype "passive"))
      (node (ref "TB2") (pin "22") (pinfunction "22_22") (pintype "passive"))
      (node (ref "U1") (pin "18") (pinfunction "ADDR_18") (pintype "input"))
    )
    (net (code "53") (name "Net-(U1-P0_0)") (class "Default")
      (node (ref "R18") (pin "1") (pinfunction "1_1") (pintype "passive"))
      (node (ref "U1") (pin "1") (pinfunction "P0_0_1") (pintype "bidirectional"))
    )
    (net (code "54") (name "Net-(U1-P0_1)") (class "Default")
      (node (ref "R19") (pin "1") (pinfunction "1_1") (pintype "passive"))
      (node (ref "U1") (pin "2") (pinfunction "P0_1_2") (pintype "bidirectional"))
    )
    (net (code "55") (name "Net-(U1-P0_2)") (class "Default")
      (node (ref "R20") (pin "1") (pinfunction "1_1") (pintype "passive"))
      (node (ref "U1") (pin "3") (pinfunction "P0_2_3") (pintype "bidirectional"))
    )
    (net (code "56") (name "Net-(U1-P0_3)") (class "Default")
      (node (ref "R25") (pin "1") (pinfunction "1_1") (pintype "passive"))
      (node (ref "U1") (pin "4") (pinfunction "P0_3_4") (pintype "bidirectional"))
    )
    (net (code "57") (name "Net-(U1-P0_4)") (class "Default")
      (node (ref "R24") (pin "1") (pinfunction "1_1") (pintype "passive"))
      (node (ref "U1") (pin "5") (pinfunction "P0_4_5") (pintype "bidirectional"))
    )
    (net (code "58") (name "Net-(U1-P0_5)") (class "Default")
      (node (ref "R23") (pin "1") (pinfunction "1_1") (pintype "passive"))
      (node (ref "U1") (pin "6") (pinfunction "P0_5_6") (pintype "bidirectional"))
    )
    (net (code "59") (name "Net-(U1-P0_6)") (class "Default")
      (node (ref "R22") (pin "1") (pinfunction "1_1") (pintype "passive"))
      (node (ref "U1") (pin "7") (pinfunction "P0_6_7") (pintype "bidirectional"))
    )
    (net (code "60") (name "Net-(U1-P0_7)") (class "Default")
      (node (ref "R21") (pin "1") (pinfunction "1_1") (pintype "passive"))
      (node (ref "U1") (pin "8") (pinfunction "P0_7_8") (pintype "bidirectional"))
    )
    (net (code "61") (name "Net-(U1-~{RESET})") (class "Default")
      (node (ref "R26") (pin "1") (pinfunction "1_1") (pintype "passive"))
      (node (ref "U1") (pin "24") (pinfunction "~{RESET}_24") (pintype "input"))
    )
    (net (code "62") (name "Net-(U2-~{INT0})") (class "Default")
      (node (ref "R30") (pin "2") (pinfunction "2_2") (pintype "passive"))
      (node (ref "U2") (pin "4") (pinfunction "~{INT0}_4") (pintype "input"))
    )
    (net (code "63") (name "Net-(U2-~{INT1})") (class "Default")
      (node (ref "R32") (pin "2") (pinfunction "2_2") (pintype "passive"))
      (node (ref "U2") (pin "8") (pinfunction "~{INT1}_8") (pintype "input"))
    )
    (net (code "64") (name "unconnected-(U1-EP-Pad25)") (class "Default")
      (node (ref "U1") (pin "25") (pinfunction "EP_25") (pintype "power_in+no_connect"))
    )
    (net (code "65") (name "unconnected-(U1-~{INT}-Pad22)") (class "Default")
      (node (ref "U1") (pin "22") (pinfunction "~{INT}_22") (pintype "open_collector+no_connect"))
    )
    (net (code "66") (name "unconnected-(U2-~{INT}-Pad11)") (class "Default")
      (node (ref "U2") (pin "11") (pinfunction "~{INT}_11") (pintype "output+no_connect"))
    )
  )
)
